# OutputLowpas.net
KiCad netlist of a schematic drawn in Altium Designer
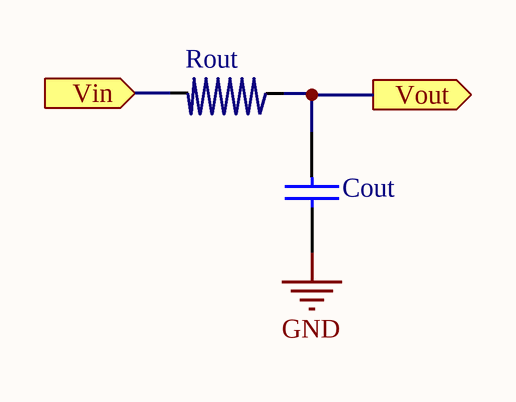
[diagram p0: OutputLowpas.SchDoc]

(export (version "E")
  (design (tool "Eeschema 10.0.6"))
  (components
    (comp (ref "Cout") (value "~") (footprint "0805") (libsource (lib "LIBEBAL") (part "CAP")))
    (comp (ref "Rout") (value "~") (footprint "PCBComponent_1") (libsource (lib "SPres") (part "SPres")))
  )
  (nets
    (net (code "1") (name "/Vin") (class "Default")
      (node (ref "Rout") (pin "1") (pinfunction "1_1") (pintype "passive"))
    )
    (net (code "2") (name "/Vout") (class "Default")
      (node (ref "Cout") (pin "1") (pinfunction "1_1") (pintype "passive"))
      (node (ref "Rout") (pin "2") (pinfunction "2_2") (pintype "passive"))
    )
    (net (code "3") (name "GND") (class "Default")
      (node (ref "Cout") (pin "2") (pinfunction "2_2") (pintype "passive"))
    )
  )
)
